# STM32H753.net
KiCad netlist of a schematic drawn in Altium Designer
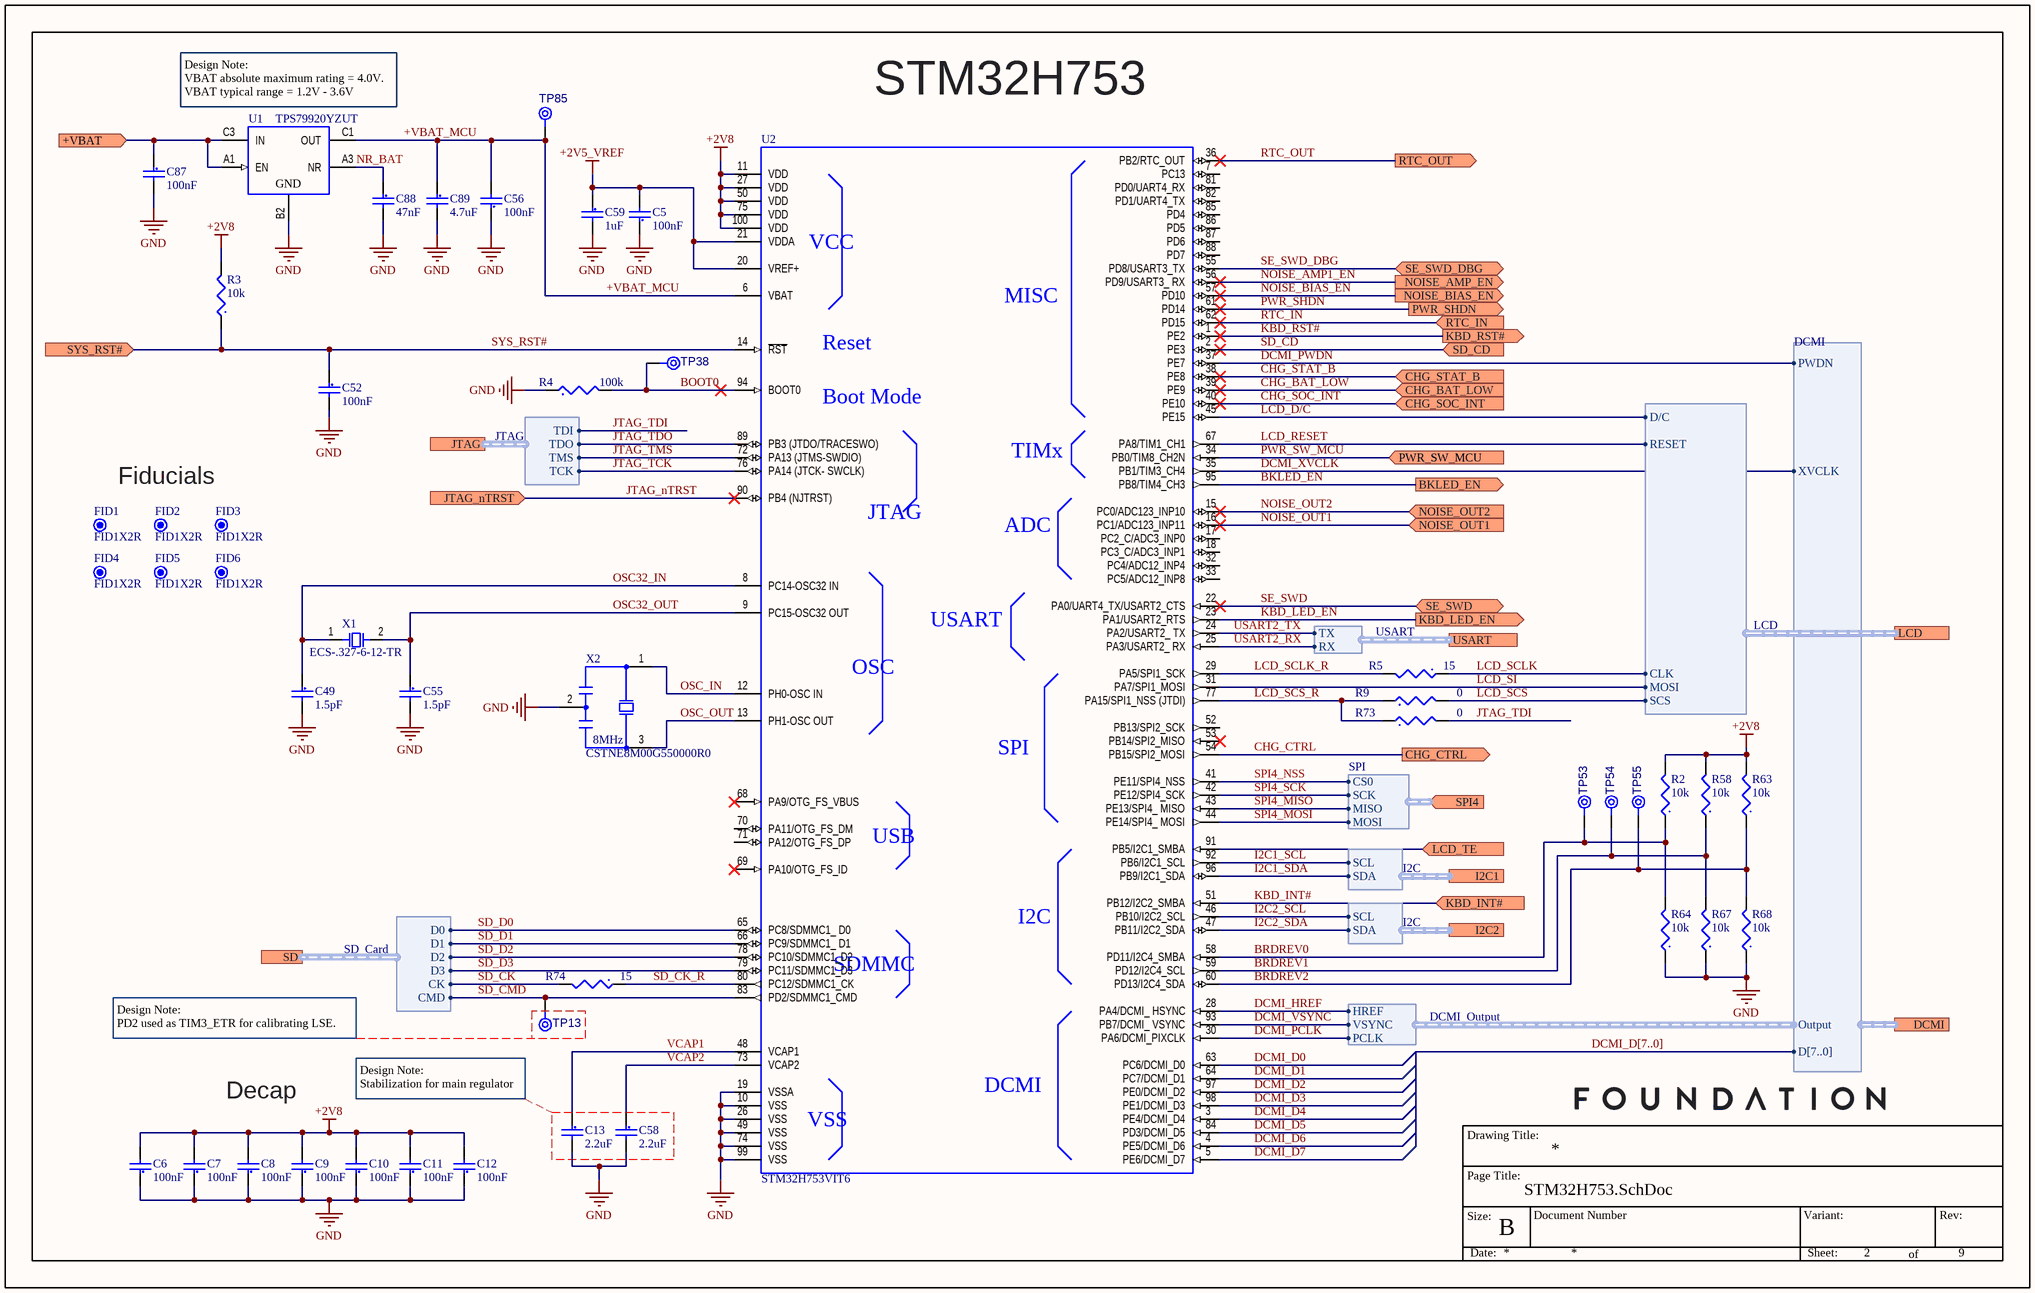
[diagram p0: STM32H753.SchDoc]

(export (version "E")
  (design (tool "Eeschema 10.0.6"))
  (components
    (comp (ref "C5")
      (value "CAP CER 0.1uF 16V 10% X7R 0402")
      (footprint "CAPC0402(1005)55_L")
      (description "0.1µF ±10% 16V Ceramic Capacitor X7R 0402 (1005 Metric)")
      (fields
        (field (name "CAPACITANCE") "100nF")
        (field (name "TOLERANCE") "10%")
        (field (name "VOLTAGE") "16V")
      )
      (libsource (lib "Altium Concord Pro on A365") (part "CAP-NP-2"))
    )
    (comp (ref "C6")
      (value "CAP CER 0.1uF 16V 10% X7R 0402")
      (footprint "CAPC0402(1005)55_L")
      (description "0.1µF ±10% 16V Ceramic Capacitor X7R 0402 (1005 Metric)")
      (fields
        (field (name "CAPACITANCE") "100nF")
        (field (name "TOLERANCE") "10%")
        (field (name "VOLTAGE") "16V")
      )
      (libsource (lib "Altium Concord Pro on A365") (part "CAP-NP-2"))
    )
    (comp (ref "C7")
      (value "CAP CER 0.1uF 16V 10% X7R 0402")
      (footprint "CAPC0402(1005)55_L")
      (description "0.1µF ±10% 16V Ceramic Capacitor X7R 0402 (1005 Metric)")
      (fields
        (field (name "CAPACITANCE") "100nF")
        (field (name "TOLERANCE") "10%")
        (field (name "VOLTAGE") "16V")
      )
      (libsource (lib "Altium Concord Pro on A365") (part "CAP-NP-2"))
    )
    (comp (ref "C8")
      (value "CAP CER 0.1uF 16V 10% X7R 0402")
      (footprint "CAPC0402(1005)55_L")
      (description "0.1µF ±10% 16V Ceramic Capacitor X7R 0402 (1005 Metric)")
      (fields
        (field (name "CAPACITANCE") "100nF")
        (field (name "TOLERANCE") "10%")
        (field (name "VOLTAGE") "16V")
      )
      (libsource (lib "Altium Concord Pro on A365") (part "CAP-NP-2"))
    )
    (comp (ref "C9")
      (value "CAP CER 0.1uF 16V 10% X7R 0402")
      (footprint "CAPC0402(1005)55_L")
      (description "0.1µF ±10% 16V Ceramic Capacitor X7R 0402 (1005 Metric)")
      (fields
        (field (name "CAPACITANCE") "100nF")
        (field (name "TOLERANCE") "10%")
        (field (name "VOLTAGE") "16V")
      )
      (libsource (lib "Altium Concord Pro on A365") (part "CAP-NP-2"))
    )
    (comp (ref "C10")
      (value "CAP CER 0.1uF 16V 10% X7R 0402")
      (footprint "CAPC0402(1005)55_L")
      (description "0.1µF ±10% 16V Ceramic Capacitor X7R 0402 (1005 Metric)")
      (fields
        (field (name "CAPACITANCE") "100nF")
        (field (name "TOLERANCE") "10%")
        (field (name "VOLTAGE") "16V")
      )
      (libsource (lib "Altium Concord Pro on A365") (part "CAP-NP-2"))
    )
    (comp (ref "C11")
      (value "CAP CER 0.1uF 16V 10% X7R 0402")
      (footprint "CAPC0402(1005)55_L")
      (description "0.1µF ±10% 16V Ceramic Capacitor X7R 0402 (1005 Metric)")
      (fields
        (field (name "CAPACITANCE") "100nF")
        (field (name "TOLERANCE") "10%")
        (field (name "VOLTAGE") "16V")
      )
      (libsource (lib "Altium Concord Pro on A365") (part "CAP-NP-2"))
    )
    (comp (ref "C12")
      (value "CAP CER 0.1uF 16V 10% X7R 0402")
      (footprint "CAPC0402(1005)55_L")
      (description "0.1µF ±10% 16V Ceramic Capacitor X7R 0402 (1005 Metric)")
      (fields
        (field (name "CAPACITANCE") "100nF")
        (field (name "TOLERANCE") "10%")
        (field (name "VOLTAGE") "16V")
      )
      (libsource (lib "Altium Concord Pro on A365") (part "CAP-NP-2"))
    )
    (comp (ref "C13")
      (value "CAP CER 2.2uF 6.3V 10% X5R 0402")
      (footprint "CAPC0402(1005)55_L")
      (description "2.2µF ±10% 6.3V Ceramic Capacitor X5R 0402 (1005 Metric)")
      (fields (field (name "CAPACITANCE") "2.2uF") (field (name "TOLERANCE") "10%"))
      (libsource (lib "Altium Concord Pro on A365") (part "CAP-NP-2"))
    )
    (comp (ref "C49")
      (value "CAP CER 1.5pF 50V C0G 0402")
      (footprint "CAPC0402(1005)55_L")
      (description "1.5pF ±0.25pF 50V Ceramic Capacitor C0G, NP0 0402 (1005 Metric)")
      (fields
        (field (name "CAPACITANCE") "1.5pF")
        (field (name "TOLERANCE") "20%")
        (field (name "VOLTAGE") "50V")
      )
      (libsource (lib "Altium Concord Pro on A365") (part "CAP-NP-2"))
    )
    (comp (ref "C52")
      (value "CAP CER 0.1uF 16V 10% X7R 0402")
      (footprint "CAPC0402(1005)55_L")
      (description "0.1µF ±10% 16V Ceramic Capacitor X7R 0402 (1005 Metric)")
      (fields
        (field (name "CAPACITANCE") "100nF")
        (field (name "VOLTAGE") "16V")
        (field (name "TOLERANCE") "10%")
      )
      (libsource (lib "Altium Concord Pro on A365") (part "CAP-NP-2"))
    )
    (comp (ref "C55")
      (value "CAP CER 1.5pF 50V C0G 0402")
      (footprint "CAPC0402(1005)55_L")
      (description "1.5pF ±0.25pF 50V Ceramic Capacitor C0G, NP0 0402 (1005 Metric)")
      (fields
        (field (name "CAPACITANCE") "1.5pF")
        (field (name "TOLERANCE") "20%")
        (field (name "VOLTAGE") "50V")
      )
      (libsource (lib "Altium Concord Pro on A365") (part "CAP-NP-2"))
    )
    (comp (ref "C56")
      (value "CAP CER 0.1uF 16V 10% X7R 0402")
      (footprint "CAPC0402(1005)55_L")
      (description "0.1µF ±10% 16V Ceramic Capacitor X7R 0402 (1005 Metric)")
      (fields
        (field (name "CAPACITANCE") "100nF")
        (field (name "TOLERANCE") "10%")
        (field (name "VOLTAGE") "16V")
      )
      (libsource (lib "Altium Concord Pro on A365") (part "CAP-NP-2"))
    )
    (comp (ref "C58")
      (value "CAP CER 2.2uF 6.3V 10% X5R 0402")
      (footprint "CAPC0402(1005)55_L")
      (description "2.2µF ±10% 6.3V Ceramic Capacitor X5R 0402 (1005 Metric)")
      (fields (field (name "CAPACITANCE") "2.2uF") (field (name "TOLERANCE") "10%"))
      (libsource (lib "Altium Concord Pro on A365") (part "CAP-NP-2"))
    )
    (comp (ref "C59")
      (value "CAP CER 1uF 25V 10% X5R 0402")
      (footprint "CAPC0402(1005)55_L")
      (description "1uF ±10% 25V Ceramic Capacitor X5R 0402 (1005 Metric)")
      (fields (field (name "CAPACITANCE") "1uF"))
      (libsource (lib "Altium Concord Pro on A365") (part "CAP-NP-2"))
    )
    (comp (ref "C87")
      (value "CAP CER 0.1uF 16V 10% X7R 0402")
      (footprint "CAPC0402(1005)55_L")
      (description "0.1µF ±10% 16V Ceramic Capacitor X7R 0402 (1005 Metric)")
      (fields
        (field (name "CAPACITANCE") "100nF")
        (field (name "TOLERANCE") "10%")
        (field (name "VOLTAGE") "16V")
      )
      (libsource (lib "Altium Concord Pro on A365") (part "CAP-NP-2"))
    )
    (comp (ref "C88")
      (value "CAP CER 0.047uF 10V 10% X7R 0402")
      (footprint "CAPC0402(1005)55_L")
      (description "0.047µF ±10% 10V Ceramic Capacitor X7R 0402 (1005 Metric)")
      (fields (field (name "CAPACITANCE") "47nF"))
      (libsource (lib "Altium Concord Pro on A365") (part "CAP-NP-2"))
    )
    (comp (ref "C89")
      (value "CAP CER 4.7UF 10V 20% X5R 0402")
      (footprint "CAPC0402(1005)55_L")
      (description "4.7µF ±20% 10V Ceramic Capacitor X5R 0402 (1005 Metric)")
      (fields
        (field (name "CAPACITANCE") "4.7uF")
        (field (name "TOLERANCE") "20%")
        (field (name "VOLTAGE") "10V")
      )
      (libsource (lib "Altium Concord Pro on A365") (part "CAP-NP-2"))
    )
    (comp (ref "FID1")
      (value "FID1X2R")
      (footprint "FID1X2R")
      (description "Fiducial - Round 1x2mm")
      (libsource (lib "Altium Concord Pro on A365") (part "FID-R-1"))
    )
    (comp (ref "FID2")
      (value "FID1X2R")
      (footprint "FID1X2R")
      (description "Fiducial - Round 1x2mm")
      (libsource (lib "Altium Concord Pro on A365") (part "FID-R-1"))
    )
    (comp (ref "FID3")
      (value "FID1X2R")
      (footprint "FID1X2R")
      (description "Fiducial - Round 1x2mm")
      (libsource (lib "Altium Concord Pro on A365") (part "FID-R-1"))
    )
    (comp (ref "FID4")
      (value "FID1X2R")
      (footprint "FID1X2R")
      (description "Fiducial - Round 1x2mm")
      (libsource (lib "Altium Concord Pro on A365") (part "FID-R-1"))
    )
    (comp (ref "FID5")
      (value "FID1X2R")
      (footprint "FID1X2R")
      (description "Fiducial - Round 1x2mm")
      (libsource (lib "Altium Concord Pro on A365") (part "FID-R-1"))
    )
    (comp (ref "FID6")
      (value "FID1X2R")
      (footprint "FID1X2R")
      (description "Fiducial - Round 1x2mm")
      (libsource (lib "Altium Concord Pro on A365") (part "FID-R-1"))
    )
    (comp (ref "R2")
      (value "RES 10K 1/16W 1% 0402")
      (footprint "RESC0402(1005)_L")
      (description "10 kOhms ±1% 0.063W, 1/16W Chip Resistor 0402 (1005 Metric)")
      (fields (field (name "RESISTANCE") "10k") (field (name "TOLERANCE") "1%"))
      (libsource (lib "Altium Concord Pro on A365") (part "RES-2"))
    )
    (comp (ref "R3")
      (value "RES 10K 1/16W 1% 0402")
      (footprint "RESC0402(1005)_L")
      (description "10 kOhms ±1% 0.063W, 1/16W Chip Resistor 0402 (1005 Metric)")
      (fields (field (name "RESISTANCE") "10k") (field (name "TOLERANCE") "1%"))
      (libsource (lib "Altium Concord Pro on A365") (part "RES-2"))
    )
    (comp (ref "R4")
      (value "RES 100K 1/16W 1% 0402")
      (footprint "RESC0402(1005)_L")
      (description "100 kOhms ±1% 0.063W, 1/16W Chip Resistor 0402 (1005 Metric) Automotive AEC-Q200 Thick Film")
      (fields (field (name "RESISTANCE") "100k") (field (name "TOLERANCE") "1%"))
      (libsource (lib "Altium Concord Pro on A365") (part "RES-2"))
    )
    (comp (ref "R5")
      (value "RES 15 OHM 1% 1/16W 0402")
      (footprint "RESC0402(1005)_L")
      (description "15 Ohms ±1% 0.063W, 1/16W Chip Resistor 0402 (1005 Metric)")
      (fields (field (name "RESISTANCE") "15") (field (name "TOLERANCE") "1%") (field (name "POWER") "63mW"))
      (libsource (lib "Altium Concord Pro on A365") (part "RES-2"))
    )
    (comp (ref "R9")
      (value "RES 0 OHM JUMPER 1/16W 0402")
      (footprint "RESC0402(1005)_L")
      (description "0 Ohms Jumper 0.063W, 1/16W Chip Resistor 0402 (1005 Metric)")
      (fields (field (name "RESISTANCE") "0") (field (name "TOLERANCE") "5%"))
      (libsource (lib "Altium Concord Pro on A365") (part "RES-2"))
    )
    (comp (ref "R58")
      (value "RES 10K 1/16W 1% 0402")
      (footprint "RESC0402(1005)_L")
      (description "10 kOhms ±1% 0.063W, 1/16W Chip Resistor 0402 (1005 Metric)")
      (fields (field (name "RESISTANCE") "10k") (field (name "TOLERANCE") "1%"))
      (libsource (lib "Altium Concord Pro on A365") (part "RES-2"))
    )
    (comp (ref "R63")
      (value "RES 10K 1/16W 1% 0402")
      (footprint "RESC0402(1005)_L")
      (description "10 kOhms ±1% 0.063W, 1/16W Chip Resistor 0402 (1005 Metric)")
      (fields (field (name "RESISTANCE") "10k") (field (name "TOLERANCE") "1%"))
      (libsource (lib "Altium Concord Pro on A365") (part "RES-2"))
    )
    (comp (ref "R64")
      (value "RES 10K 1/16W 1% 0402")
      (footprint "RESC0402(1005)_L")
      (description "10 kOhms ±1% 0.063W, 1/16W Chip Resistor 0402 (1005 Metric)")
      (fields (field (name "RESISTANCE") "10k") (field (name "TOLERANCE") "1%"))
      (libsource (lib "Altium Concord Pro on A365") (part "RES-2"))
    )
    (comp (ref "R67")
      (value "RES 10K 1/16W 1% 0402")
      (footprint "RESC0402(1005)_L")
      (description "10 kOhms ±1% 0.063W, 1/16W Chip Resistor 0402 (1005 Metric)")
      (fields (field (name "RESISTANCE") "10k") (field (name "TOLERANCE") "1%"))
      (libsource (lib "Altium Concord Pro on A365") (part "RES-2"))
    )
    (comp (ref "R68")
      (value "RES 10K 1/16W 1% 0402")
      (footprint "RESC0402(1005)_L")
      (description "10 kOhms ±1% 0.063W, 1/16W Chip Resistor 0402 (1005 Metric)")
      (fields (field (name "RESISTANCE") "10k") (field (name "TOLERANCE") "1%"))
      (libsource (lib "Altium Concord Pro on A365") (part "RES-2"))
    )
    (comp (ref "R73")
      (value "RES 0 OHM JUMPER 1/16W 0402")
      (footprint "RESC0402(1005)_L")
      (description "0 Ohms Jumper 0.063W, 1/16W Chip Resistor 0402 (1005 Metric)")
      (fields (field (name "RESISTANCE") "0") (field (name "TOLERANCE") "5%"))
      (libsource (lib "Altium Concord Pro on A365") (part "RES-2"))
    )
    (comp (ref "R74")
      (value "RES 15 OHM 1% 1/16W 0402")
      (footprint "RESC0402(1005)_L")
      (description "15 Ohms ±1% 0.063W, 1/16W Chip Resistor 0402 (1005 Metric)")
      (fields (field (name "RESISTANCE") "15") (field (name "TOLERANCE") "1%") (field (name "POWER") "63mW"))
      (libsource (lib "Altium Concord Pro on A365") (part "RES-2"))
    )
    (comp (ref "TP13")
      (value "TPAD8R")
      (footprint "TP08R")
      (description "0.8mm round")
      (libsource (lib "Altium Concord Pro on A365") (part "TP-R-1"))
    )
    (comp (ref "TP38")
      (value "TPAD8R")
      (footprint "TP08R")
      (description "0.8mm round")
      (libsource (lib "Altium Concord Pro on A365") (part "TP-R-1"))
    )
    (comp (ref "TP53")
      (value "TPAD8R")
      (footprint "TP08R")
      (description "0.8mm round")
      (libsource (lib "Altium Concord Pro on A365") (part "TP-R-1"))
    )
    (comp (ref "TP54")
      (value "TPAD8R")
      (footprint "TP08R")
      (description "0.8mm round")
      (libsource (lib "Altium Concord Pro on A365") (part "TP-R-1"))
    )
    (comp (ref "TP55")
      (value "TPAD8R")
      (footprint "TP08R")
      (description "0.8mm round")
      (libsource (lib "Altium Concord Pro on A365") (part "TP-R-1"))
    )
    (comp (ref "TP85")
      (value "TPAD8R")
      (footprint "TP08R")
      (description "0.8mm round")
      (libsource (lib "Altium Concord Pro on A365") (part "TP-R-1"))
    )
    (comp (ref "U1")
      (value "TPS79920YZUT")
      (footprint "TI - DSBGA-YZU-5_V")
      (description "Linear Voltage Regulator IC Positive Fixed 1 Output 2.0V 200mA 5-DSBGA (1x1.37)")
      (libsource (lib "Altium Concord Pro on A365") (part "TPS79928YZU"))
    )
    (comp (ref "U2")
      (value "STM32H753VIT6")
      (footprint "STM - LQFP-100_L")
      (description "ARM® Cortex®-M7 STM32H7 Microcontroller IC 32-Bit 480MHz 2MB (2M x 8) FLASH 100-LQFP (14x14)")
      (libsource (lib "Altium Concord Pro on A365") (part "STM32H743VIT6"))
    )
    (comp (ref "X1")
      (value "ECS-.327-6-12-TR")
      (footprint "ECS - ECX-12_V")
      (description "Parallel - Fundamental Quartz Crystal, 0.032768MHz Nom")
      (libsource (lib "Altium Concord Pro on A365") (part "XTAL-2"))
    )
    (comp (ref "X2")
      (value "CSTNE8M00G550000R0")
      (footprint "MURA - CSTNE_V")
      (description "8MHz Ceramic Resonator Built in Capacitor 33pF ±0.2% 40 Ohms -40°C ~ 85°C Surface Mount")
      (fields (field (name "FREQUENCY") "8MHz"))
      (libsource (lib "Altium Concord Pro on A365") (part "XTAL-3-13-INTC"))
    )
  )
  (nets
    (net (code "9") (name "+2V5_VREF") (class "Default")
      (node (ref "C5") (pin "2") (pinfunction "2_2") (pintype "passive"))
      (node (ref "C59") (pin "1") (pinfunction "1_1") (pintype "passive"))
      (node (ref "U2") (pin "20") (pinfunction "VREF+_20") (pintype "power_in"))
      (node (ref "U2") (pin "21") (pinfunction "VDDA_21") (pintype "power_in"))
    )
    (net (code "10") (name "+2V8") (class "Default")
      (node (ref "C10") (pin "2") (pinfunction "2_2") (pintype "passive"))
      (node (ref "C11") (pin "2") (pinfunction "2_2") (pintype "passive"))
      (node (ref "C12") (pin "2") (pinfunction "2_2") (pintype "passive"))
      (node (ref "C6") (pin "2") (pinfunction "2_2") (pintype "passive"))
      (node (ref "C7") (pin "2") (pinfunction "2_2") (pintype "passive"))
      (node (ref "C8") (pin "2") (pinfunction "2_2") (pintype "passive"))
      (node (ref "C9") (pin "2") (pinfunction "2_2") (pintype "passive"))
      (node (ref "R2") (pin "2") (pinfunction "2_2") (pintype "passive"))
      (node (ref "R3") (pin "2") (pinfunction "2_2") (pintype "passive"))
      (node (ref "R58") (pin "2") (pinfunction "2_2") (pintype "passive"))
      (node (ref "R63") (pin "2") (pinfunction "2_2") (pintype "passive"))
      (node (ref "U2") (pin "100") (pinfunction "VDD_100") (pintype "power_in"))
      (node (ref "U2") (pin "11") (pinfunction "VDD_11") (pintype "power_in"))
      (node (ref "U2") (pin "27") (pinfunction "VDD_27") (pintype "power_in"))
      (node (ref "U2") (pin "50") (pinfunction "VDD_50") (pintype "power_in"))
      (node (ref "U2") (pin "75") (pinfunction "VDD_75") (pintype "power_in"))
    )
    (net (code "11") (name "/+VBAT") (class "Default")
      (node (ref "C87") (pin "1") (pinfunction "1_1") (pintype "passive"))
      (node (ref "U1") (pin "A1") (pinfunction "EN_A1") (pintype "input"))
      (node (ref "U1") (pin "C3") (pinfunction "IN_C3") (pintype "power_in"))
    )
    (net (code "12") (name "/+VBAT_MCU") (class "Default")
      (node (ref "C56") (pin "2") (pinfunction "2_2") (pintype "passive"))
      (node (ref "C89") (pin "1") (pinfunction "1_1") (pintype "passive"))
      (node (ref "TP85") (pin "1") (pinfunction "TP_1") (pintype "passive"))
      (node (ref "U1") (pin "C1") (pinfunction "OUT_C1") (pintype "power_in"))
      (node (ref "U2") (pin "6") (pinfunction "VBAT_6") (pintype "power_in"))
    )
    (net (code "13") (name "/BKLED_EN") (class "Default")
      (node (ref "U2") (pin "95") (pinfunction "PB8/TIM4_CH3_95") (pintype "output"))
    )
    (net (code "14") (name "/BOOT0") (class "Default")
      (node (ref "R4") (pin "2") (pinfunction "2_2") (pintype "passive"))
      (node (ref "TP38") (pin "1") (pinfunction "TP_1") (pintype "passive"))
      (node (ref "U2") (pin "94") (pinfunction "BOOT0_94") (pintype "input"))
    )
    (net (code "15") (name "/BRDREV0") (class "Default")
      (node (ref "R2") (pin "1") (pinfunction "1_1") (pintype "passive"))
      (node (ref "R64") (pin "2") (pinfunction "2_2") (pintype "passive"))
      (node (ref "TP53") (pin "1") (pinfunction "TP_1") (pintype "passive"))
      (node (ref "U2") (pin "58") (pinfunction "PD11/I2C4_SMBA_58") (pintype "input"))
    )
    (net (code "16") (name "/BRDREV1") (class "Default")
      (node (ref "R58") (pin "1") (pinfunction "1_1") (pintype "passive"))
      (node (ref "R67") (pin "2") (pinfunction "2_2") (pintype "passive"))
      (node (ref "TP54") (pin "1") (pinfunction "TP_1") (pintype "passive"))
      (node (ref "U2") (pin "59") (pinfunction "PD12/I2C4_SCL_59") (pintype "output"))
    )
    (net (code "17") (name "/BRDREV2") (class "Default")
      (node (ref "R63") (pin "1") (pinfunction "1_1") (pintype "passive"))
      (node (ref "R68") (pin "2") (pinfunction "2_2") (pintype "passive"))
      (node (ref "TP55") (pin "1") (pinfunction "TP_1") (pintype "passive"))
      (node (ref "U2") (pin "60") (pinfunction "PD13/I2C4_SDA_60") (pintype "bidirectional"))
    )
    (net (code "18") (name "/CHG_BAT_LOW") (class "Default")
      (node (ref "U2") (pin "39") (pinfunction "PE9_39") (pintype "bidirectional+no_connect"))
    )
    (net (code "19") (name "/CHG_CTRL") (class "Default")
      (node (ref "U2") (pin "54") (pinfunction "PB15/SPI2_MOSI_54") (pintype "output"))
    )
    (net (code "20") (name "/CHG_SOC_INT") (class "Default")
      (node (ref "U2") (pin "40") (pinfunction "PE10_40") (pintype "bidirectional+no_connect"))
    )
    (net (code "21") (name "/CHG_STAT_B") (class "Default")
      (node (ref "U2") (pin "38") (pinfunction "PE8_38") (pintype "bidirectional+no_connect"))
    )
    (net (code "22") (name "/DCMI_D0") (class "Default")
      (node (ref "U2") (pin "63") (pinfunction "PC6/DCMI_D0_63") (pintype "input"))
    )
    (net (code "23") (name "/DCMI_D1") (class "Default")
      (node (ref "U2") (pin "64") (pinfunction "PC7/DCMI_D1_64") (pintype "input"))
    )
    (net (code "24") (name "/DCMI_D2") (class "Default")
      (node (ref "U2") (pin "97") (pinfunction "PE0/DCMI_D2_97") (pintype "input"))
    )
    (net (code "25") (name "/DCMI_D3") (class "Default")
      (node (ref "U2") (pin "98") (pinfunction "PE1/DCMI_D3_98") (pintype "input"))
    )
    (net (code "26") (name "/DCMI_D4") (class "Default")
      (node (ref "U2") (pin "3") (pinfunction "PE4/DCMI_D4_3") (pintype "input"))
    )
    (net (code "27") (name "/DCMI_D5") (class "Default")
      (node (ref "U2") (pin "84") (pinfunction "PD3/DCMI_D5_84") (pintype "input"))
    )
    (net (code "28") (name "/DCMI_D6") (class "Default")
      (node (ref "U2") (pin "4") (pinfunction "PE5/DCMI_D6_4") (pintype "input"))
    )
    (net (code "29") (name "/DCMI_D7") (class "Default")
      (node (ref "U2") (pin "5") (pinfunction "PE6/DCMI_D7_5") (pintype "input"))
    )
    (net (code "31") (name "/DCMI_HREF") (class "Default")
      (node (ref "U2") (pin "28") (pinfunction "PA4/DCMI__HSYNC_28") (pintype "input"))
    )
    (net (code "32") (name "/DCMI_PCLK") (class "Default")
      (node (ref "U2") (pin "30") (pinfunction "PA6/DCMI_PIXCLK_30") (pintype "input"))
    )
    (net (code "33") (name "/DCMI_PWDN") (class "Default")
      (node (ref "U2") (pin "37") (pinfunction "PE7_37") (pintype "bidirectional"))
    )
    (net (code "34") (name "/DCMI_VSYNC") (class "Default")
      (node (ref "U2") (pin "93") (pinfunction "PB7/DCMI__VSYNC_93") (pintype "input"))
    )
    (net (code "35") (name "/DCMI_XVCLK") (class "Default")
      (node (ref "U2") (pin "35") (pinfunction "PB1/TIM3_CH4_35") (pintype "output"))
    )
    (net (code "36") (name "/I2C1_SCL") (class "Default")
      (node (ref "U2") (pin "92") (pinfunction "PB6/I2C1_SCL_92") (pintype "output"))
    )
    (net (code "37") (name "/I2C1_SDA") (class "Default")
      (node (ref "U2") (pin "96") (pinfunction "PB9/I2C1_SDA_96") (pintype "bidirectional"))
    )
    (net (code "38") (name "/I2C2_SCL") (class "Default")
      (node (ref "U2") (pin "46") (pinfunction "PB10/I2C2_SCL_46") (pintype "output"))
    )
    (net (code "39") (name "/I2C2_SDA") (class "Default")
      (node (ref "U2") (pin "47") (pinfunction "PB11/I2C2_SDA_47") (pintype "bidirectional"))
    )
    (net (code "40") (name "/JTAG_TCK") (class "Default")
      (node (ref "U2") (pin "76") (pinfunction "PA14_(JTCK-_SWCLK)_76") (pintype "bidirectional"))
    )
    (net (code "41") (name "/JTAG_TDI") (class "Default")
      (node (ref "R73") (pin "2") (pinfunction "2_2") (pintype "passive"))
    )
    (net (code "42") (name "/JTAG_TDO") (class "Default")
      (node (ref "U2") (pin "89") (pinfunction "PB3_(JTDO/TRACESWO)_89") (pintype "bidirectional"))
    )
    (net (code "43") (name "/JTAG_TMS") (class "Default")
      (node (ref "U2") (pin "72") (pinfunction "PA13_(JTMS-SWDIO)_72") (pintype "bidirectional"))
    )
    (net (code "44") (name "/JTAG_nTRST") (class "Default")
      (node (ref "U2") (pin "90") (pinfunction "PB4_(NJTRST)_90") (pintype "bidirectional+no_connect"))
    )
    (net (code "45") (name "/KBD_INT#") (class "Default")
      (node (ref "U2") (pin "51") (pinfunction "PB12/I2C2_SMBA_51") (pintype "input"))
    )
    (net (code "46") (name "/KBD_LED_EN") (class "Default")
      (node (ref "U2") (pin "23") (pinfunction "PA1/USART2_RTS_23") (pintype "output"))
    )
    (net (code "47") (name "/KBD_RST#") (class "Default")
      (node (ref "U2") (pin "1") (pinfunction "PE2_1") (pintype "bidirectional+no_connect"))
    )
    (net (code "48") (name "/LCD_D{slash}C") (class "Default")
      (node (ref "U2") (pin "45") (pinfunction "PE15_45") (pintype "bidirectional"))
    )
    (net (code "49") (name "/LCD_RESET") (class "Default")
      (node (ref "U2") (pin "67") (pinfunction "PA8/TIM1_CH1_67") (pintype "output"))
    )
    (net (code "50") (name "/LCD_SCLK") (class "Default")
      (node (ref "R5") (pin "1") (pinfunction "1_1") (pintype "passive"))
    )
    (net (code "51") (name "/LCD_SCLK_R") (class "Default")
      (node (ref "R5") (pin "2") (pinfunction "2_2") (pintype "passive"))
      (node (ref "U2") (pin "29") (pinfunction "PA5/SPI1_SCK_29") (pintype "output"))
    )
    (net (code "52") (name "/LCD_SCS") (class "Default")
      (node (ref "R9") (pin "2") (pinfunction "2_2") (pintype "passive"))
    )
    (net (code "53") (name "/LCD_SCS_R") (class "Default")
      (node (ref "R73") (pin "1") (pinfunction "1_1") (pintype "passive"))
      (node (ref "R9") (pin "1") (pinfunction "1_1") (pintype "passive"))
      (node (ref "U2") (pin "77") (pinfunction "PA15/SPI1_NSS_(JTDI)_77") (pintype "output"))
    )
    (net (code "54") (name "/LCD_SI") (class "Default")
      (node (ref "U2") (pin "31") (pinfunction "PA7/SPI1_MOSI_31") (pintype "output"))
    )
    (net (code "55") (name "/LCD_TE") (class "Default")
      (node (ref "U2") (pin "91") (pinfunction "PB5/I2C1_SMBA_91") (pintype "input"))
    )
    (net (code "56") (name "/NOISE_AMP1_EN") (class "Default")
      (node (ref "U2") (pin "56") (pinfunction "PD9/USART3__RX_56") (pintype "bidirectional+no_connect"))
    )
    (net (code "57") (name "/NOISE_BIAS_EN") (class "Default")
      (node (ref "U2") (pin "57") (pinfunction "PD10_57") (pintype "bidirectional+no_connect"))
    )
    (net (code "58") (name "/NOISE_OUT1") (class "Default")
      (node (ref "U2") (pin "16") (pinfunction "PC1/ADC123_INP11_16") (pintype "bidirectional+no_connect"))
    )
    (net (code "59") (name "/NOISE_OUT2") (class "Default")
      (node (ref "U2") (pin "15") (pinfunction "PC0/ADC123_INP10_15") (pintype "bidirectional+no_connect"))
    )
    (net (code "60") (name "/NR_BAT") (class "Default")
      (node (ref "C88") (pin "1") (pinfunction "1_1") (pintype "passive"))
      (node (ref "U1") (pin "A3") (pinfunction "NR_A3") (pintype "passive"))
    )
    (net (code "61") (name "/OSC32_IN") (class "Default")
      (node (ref "C49") (pin "1") (pinfunction "1_1") (pintype "passive"))
      (node (ref "U2") (pin "8") (pinfunction "PC14-OSC32_IN_8") (pintype "passive"))
      (node (ref "X1") (pin "1") (pinfunction "1_1") (pintype "passive"))
    )
    (net (code "62") (name "/OSC32_OUT") (class "Default")
      (node (ref "C55") (pin "1") (pinfunction "1_1") (pintype "passive"))
      (node (ref "U2") (pin "9") (pinfunction "PC15-OSC32_OUT_9") (pintype "passive"))
      (node (ref "X1") (pin "2") (pinfunction "2_2") (pintype "passive"))
    )
    (net (code "63") (name "/OSC_IN") (class "Default")
      (node (ref "U2") (pin "12") (pinfunction "PH0-OSC_IN_12") (pintype "passive"))
      (node (ref "X2") (pin "1") (pinfunction "1_1") (pintype "passive"))
    )
    (net (code "64") (name "/OSC_OUT") (class "Default")
      (node (ref "U2") (pin "13") (pinfunction "PH1-OSC_OUT_13") (pintype "passive"))
      (node (ref "X2") (pin "3") (pinfunction "3_3") (pintype "passive"))
    )
    (net (code "65") (name "/PWR_SHDN") (class "Default")
      (node (ref "U2") (pin "61") (pinfunction "PD14_61") (pintype "bidirectional+no_connect"))
    )
    (net (code "66") (name "/PWR_SW_MCU") (class "Default")
      (node (ref "U2") (pin "34") (pinfunction "PB0/TIM8_CH2N_34") (pintype "input"))
    )
    (net (code "67") (name "/RTC_IN") (class "Default")
      (node (ref "U2") (pin "62") (pinfunction "PD15_62") (pintype "bidirectional+no_connect"))
    )
    (net (code "68") (name "/RTC_OUT") (class "Default")
      (node (ref "U2") (pin "36") (pinfunction "PB2/RTC_OUT_36") (pintype "bidirectional+no_connect"))
    )
    (net (code "69") (name "/SD_CD") (class "Default")
      (node (ref "U2") (pin "2") (pinfunction "PE3_2") (pintype "bidirectional+no_connect"))
    )
    (net (code "70") (name "/SD_CK") (class "Default")
      (node (ref "R74") (pin "2") (pinfunction "2_2") (pintype "passive"))
    )
    (net (code "71") (name "/SD_CK_R") (class "Default")
      (node (ref "R74") (pin "1") (pinfunction "1_1") (pintype "passive"))
      (node (ref "U2") (pin "80") (pinfunction "PC12/SDMMC1_CK_80") (pintype "output"))
    )
    (net (code "72") (name "/SD_CMD") (class "Default")
      (node (ref "TP13") (pin "1") (pinfunction "TP_1") (pintype "passive"))
      (node (ref "U2") (pin "83") (pinfunction "PD2/SDMMC1_CMD_83") (pintype "output"))
    )
    (net (code "73") (name "/SD_D0") (class "Default")
      (node (ref "U2") (pin "65") (pinfunction "PC8/SDMMC1__D0_65") (pintype "bidirectional"))
    )
    (net (code "74") (name "/SD_D1") (class "Default")
      (node (ref "U2") (pin "66") (pinfunction "PC9/SDMMC1__D1_66") (pintype "bidirectional"))
    )
    (net (code "75") (name "/SD_D2") (class "Default")
      (node (ref "U2") (pin "78") (pinfunction "PC10/SDMMC1_D2_78") (pintype "bidirectional"))
    )
    (net (code "76") (name "/SD_D3") (class "Default")
      (node (ref "U2") (pin "79") (pinfunction "PC11/SDMMC1_D3_79") (pintype "bidirectional"))
    )
    (net (code "77") (name "/SE_SWD") (class "Default")
      (node (ref "U2") (pin "22") (pinfunction "PA0/UART4_TX/USART2_CTS_22") (pintype "input+no_connect"))
    )
    (net (code "78") (name "/SE_SWD_DBG") (class "Default")
      (node (ref "U2") (pin "55") (pinfunction "PD8/USART3_TX_55") (pintype "bidirectional"))
    )
    (net (code "79") (name "/SPI4_MISO") (class "Default")
      (node (ref "U2") (pin "43") (pinfunction "PE13/SPI4__MISO_43") (pintype "input"))
    )
    (net (code "80") (name "/SPI4_MOSI") (class "Default")
      (node (ref "U2") (pin "44") (pinfunction "PE14/SPI4__MOSI_44") (pintype "output"))
    )
    (net (code "81") (name "/SPI4_NSS") (class "Default")
      (node (ref "U2") (pin "41") (pinfunction "PE11/SPI4_NSS_41") (pintype "output"))
    )
    (net (code "82") (name "/SPI4_SCK") (class "Default")
      (node (ref "U2") (pin "42") (pinfunction "PE12/SPI4_SCK_42") (pintype "output"))
    )
    (net (code "83") (name "/SYS_RST#") (class "Default")
      (node (ref "C52") (pin "1") (pinfunction "1_1") (pintype "passive"))
      (node (ref "R3") (pin "1") (pinfunction "1_1") (pintype "passive"))
      (node (ref "U2") (pin "14") (pinfunction "~{RST}_14") (pintype "input"))
    )
    (net (code "84") (name "/USART2_RX") (class "Default")
      (node (ref "U2") (pin "25") (pinfunction "PA3/USART2__RX_25") (pintype "input"))
    )
    (net (code "85") (name "/USART2_TX") (class "Default")
      (node (ref "U2") (pin "24") (pinfunction "PA2/USART2__TX_24") (pintype "output"))
    )
    (net (code "86") (name "/VCAP1") (class "Default")
      (node (ref "C13") (pin "1") (pinfunction "1_1") (pintype "passive"))
      (node (ref "U2") (pin "48") (pinfunction "VCAP1_48") (pintype "passive"))
    )
    (net (code "87") (name "/VCAP2") (class "Default")
      (node (ref "C58") (pin "1") (pinfunction "1_1") (pintype "passive"))
      (node (ref "U2") (pin "73") (pinfunction "VCAP2_73") (pintype "passive"))
    )
    (net (code "96") (name "GND") (class "Default")
      (node (ref "C10") (pin "1") (pinfunction "1_1") (pintype "passive"))
      (node (ref "C11") (pin "1") (pinfunction "1_1") (pintype "passive"))
      (node (ref "C12") (pin "1") (pinfunction "1_1") (pintype "passive"))
      (node (ref "C13") (pin "2") (pinfunction "2_2") (pintype "passive"))
      (node (ref "C49") (pin "2") (pinfunction "2_2") (pintype "passive"))
      (node (ref "C5") (pin "1") (pinfunction "1_1") (pintype "passive"))
      (node (ref "C52") (pin "2") (pinfunction "2_2") (pintype "passive"))
      (node (ref "C55") (pin "2") (pinfunction "2_2") (pintype "passive"))
      (node (ref "C56") (pin "1") (pinfunction "1_1") (pintype "passive"))
      (node (ref "C58") (pin "2") (pinfunction "2_2") (pintype "passive"))
      (node (ref "C59") (pin "2") (pinfunction "2_2") (pintype "passive"))
      (node (ref "C6") (pin "1") (pinfunction "1_1") (pintype "passive"))
      (node (ref "C7") (pin "1") (pinfunction "1_1") (pintype "passive"))
      (node (ref "C8") (pin "1") (pinfunction "1_1") (pintype "passive"))
      (node (ref "C87") (pin "2") (pinfunction "2_2") (pintype "passive"))
      (node (ref "C88") (pin "2") (pinfunction "2_2") (pintype "passive"))
      (node (ref "C89") (pin "2") (pinfunction "2_2") (pintype "passive"))
      (node (ref "C9") (pin "1") (pinfunction "1_1") (pintype "passive"))
      (node (ref "R4") (pin "1") (pinfunction "1_1") (pintype "passive"))
      (node (ref "R64") (pin "1") (pinfunction "1_1") (pintype "passive"))
      (node (ref "R67") (pin "1") (pinfunction "1_1") (pintype "passive"))
      (node (ref "R68") (pin "1") (pinfunction "1_1") (pintype "passive"))
      (node (ref "U1") (pin "B2") (pinfunction "GND_B2") (pintype "power_in"))
      (node (ref "U2") (pin "10") (pinfunction "VSS_10") (pintype "power_in"))
      (node (ref "U2") (pin "19") (pinfunction "VSSA_19") (pintype "power_in"))
      (node (ref "U2") (pin "26") (pinfunction "VSS_26") (pintype "power_in"))
      (node (ref "U2") (pin "49") (pinfunction "VSS_49") (pintype "power_in"))
      (node (ref "U2") (pin "74") (pinfunction "VSS_74") (pintype "power_in"))
      (node (ref "U2") (pin "99") (pinfunction "VSS_99") (pintype "power_in"))
      (node (ref "X2") (pin "2") (pinfunction "GND_2") (pintype "passive"))
    )
    (net (code "97") (name "unconnected-(U2-PA9{slash}OTG_FS_VBUS-Pad68)") (class "Default")
      (node (ref "U2") (pin "68") (pinfunction "PA9/OTG_FS_VBUS_68") (pintype "input+no_connect"))
    )
    (net (code "98") (name "unconnected-(U2-PA10{slash}OTG_FS_ID-Pad69)") (class "Default")
      (node (ref "U2") (pin "69") (pinfunction "PA10/OTG_FS_ID_69") (pintype "input+no_connect"))
    )
    (net (code "99") (name "unconnected-(U2-PA11{slash}OTG_FS_DM-Pad70)") (class "Default")
      (node (ref "U2") (pin "70") (pinfunction "PA11/OTG_FS_DM_70") (pintype "bidirectional"))
    )
    (net (code "100") (name "unconnected-(U2-PA12{slash}OTG_FS_DP-Pad71)") (class "Default")
      (node (ref "U2") (pin "71") (pinfunction "PA12/OTG_FS_DP_71") (pintype "bidirectional"))
    )
    (net (code "101") (name "unconnected-(U2-PB13{slash}SPI2_SCK-Pad52)") (class "Default")
      (node (ref "U2") (pin "52") (pinfunction "PB13/SPI2_SCK_52") (pintype "output"))
    )
    (net (code "102") (name "unconnected-(U2-PB14{slash}SPI2_MISO-Pad53)") (class "Default")
      (node (ref "U2") (pin "53") (pinfunction "PB14/SPI2_MISO_53") (pintype "input+no_connect"))
    )
    (net (code "103") (name "unconnected-(U2-PC2_C{slash}ADC3_INP0-Pad17)") (class "Default")
      (node (ref "U2") (pin "17") (pinfunction "PC2_C/ADC3_INP0_17") (pintype "bidirectional"))
    )
    (net (code "104") (name "unconnected-(U2-PC3_C{slash}ADC3_INP1-Pad18)") (class "Default")
      (node (ref "U2") (pin "18") (pinfunction "PC3_C/ADC3_INP1_18") (pintype "bidirectional"))
    )
    (net (code "105") (name "unconnected-(U2-PC4{slash}ADC12_INP4-Pad32)") (class "Default")
      (node (ref "U2") (pin "32") (pinfunction "PC4/ADC12_INP4_32") (pintype "bidirectional"))
    )
    (net (code "106") (name "unconnected-(U2-PC5{slash}ADC12_INP8-Pad33)") (class "Default")
      (node (ref "U2") (pin "33") (pinfunction "PC5/ADC12_INP8_33") (pintype "bidirectional"))
    )
    (net (code "107") (name "unconnected-(U2-PC13-Pad7)") (class "Default")
      (node (ref "U2") (pin "7") (pinfunction "PC13_7") (pintype "bidirectional"))
    )
    (net (code "108") (name "unconnected-(U2-PD0{slash}UART4_RX-Pad81)") (class "Default")
      (node (ref "U2") (pin "81") (pinfunction "PD0/UART4_RX_81") (pintype "bidirectional"))
    )
    (net (code "109") (name "unconnected-(U2-PD1{slash}UART4_TX-Pad82)") (class "Default")
      (node (ref "U2") (pin "82") (pinfunction "PD1/UART4_TX_82") (pintype "bidirectional"))
    )
    (net (code "110") (name "unconnected-(U2-PD4-Pad85)") (class "Default")
      (node (ref "U2") (pin "85") (pinfunction "PD4_85") (pintype "bidirectional"))
    )
    (net (code "111") (name "unconnected-(U2-PD5-Pad86)") (class "Default")
      (node (ref "U2") (pin "86") (pinfunction "PD5_86") (pintype "bidirectional"))
    )
    (net (code "112") (name "unconnected-(U2-PD6-Pad87)") (class "Default")
      (node (ref "U2") (pin "87") (pinfunction "PD6_87") (pintype "bidirectional"))
    )
    (net (code "113") (name "unconnected-(U2-PD7-Pad88)") (class "Default")
      (node (ref "U2") (pin "88") (pinfunction "PD7_88") (pintype "bidirectional"))
    )
  )
)
